# adc.net
KiCad netlist of a schematic drawn in Altium Designer
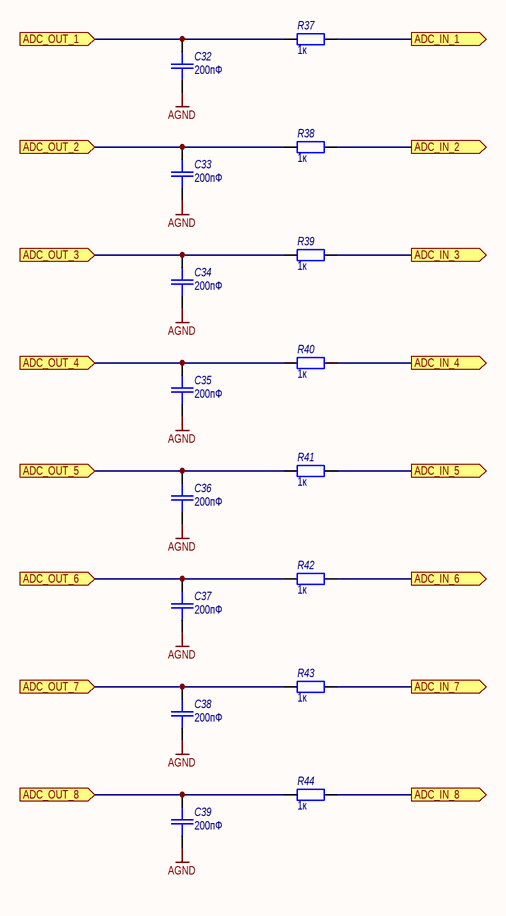
[diagram p0: adc.SchDoc]

(export (version "E")
  (design (tool "Eeschema 10.0.6"))
  (components
    (comp (ref "C32")
      (value "200пФ")
      (footprint "SMD_0805")
      (description "Capacitor")
      (libsource (lib "Passive") (part "Capacitor"))
    )
    (comp (ref "C33")
      (value "200пФ")
      (footprint "SMD_0805")
      (description "Capacitor")
      (libsource (lib "Passive") (part "Capacitor"))
    )
    (comp (ref "C34")
      (value "200пФ")
      (footprint "SMD_0805")
      (description "Capacitor")
      (libsource (lib "Passive") (part "Capacitor"))
    )
    (comp (ref "C35")
      (value "200пФ")
      (footprint "SMD_0805")
      (description "Capacitor")
      (libsource (lib "Passive") (part "Capacitor"))
    )
    (comp (ref "C36")
      (value "200пФ")
      (footprint "SMD_0805")
      (description "Capacitor")
      (libsource (lib "Passive") (part "Capacitor"))
    )
    (comp (ref "C37")
      (value "200пФ")
      (footprint "SMD_0805")
      (description "Capacitor")
      (libsource (lib "Passive") (part "Capacitor"))
    )
    (comp (ref "C38")
      (value "200пФ")
      (footprint "SMD_0805")
      (description "Capacitor")
      (libsource (lib "Passive") (part "Capacitor"))
    )
    (comp (ref "C39")
      (value "200пФ")
      (footprint "SMD_0805")
      (description "Capacitor")
      (libsource (lib "Passive") (part "Capacitor"))
    )
    (comp (ref "R37")
      (value "1к")
      (footprint "SMD_0805")
      (description "Resistor")
      (libsource (lib "Passive") (part "Resistor"))
    )
    (comp (ref "R38")
      (value "1к")
      (footprint "SMD_0805")
      (description "Resistor")
      (libsource (lib "Passive") (part "Resistor"))
    )
    (comp (ref "R39")
      (value "1к")
      (footprint "SMD_0805")
      (description "Resistor")
      (libsource (lib "Passive") (part "Resistor"))
    )
    (comp (ref "R40")
      (value "1к")
      (footprint "SMD_0805")
      (description "Resistor")
      (libsource (lib "Passive") (part "Resistor"))
    )
    (comp (ref "R41")
      (value "1к")
      (footprint "SMD_0805")
      (description "Resistor")
      (libsource (lib "Passive") (part "Resistor"))
    )
    (comp (ref "R42")
      (value "1к")
      (footprint "SMD_0805")
      (description "Resistor")
      (libsource (lib "Passive") (part "Resistor"))
    )
    (comp (ref "R43")
      (value "1к")
      (footprint "SMD_0805")
      (description "Resistor")
      (libsource (lib "Passive") (part "Resistor"))
    )
    (comp (ref "R44")
      (value "1к")
      (footprint "SMD_0805")
      (description "Resistor")
      (libsource (lib "Passive") (part "Resistor"))
    )
  )
  (nets
    (net (code "1") (name "/ADC_IN_1") (class "Default")
      (node (ref "R37") (pin "2") (pinfunction "2_2") (pintype "passive"))
    )
    (net (code "2") (name "/ADC_IN_2") (class "Default")
      (node (ref "R38") (pin "2") (pinfunction "2_2") (pintype "passive"))
    )
    (net (code "3") (name "/ADC_IN_3") (class "Default")
      (node (ref "R39") (pin "2") (pinfunction "2_2") (pintype "passive"))
    )
    (net (code "4") (name "/ADC_IN_4") (class "Default")
      (node (ref "R40") (pin "2") (pinfunction "2_2") (pintype "passive"))
    )
    (net (code "5") (name "/ADC_IN_5") (class "Default")
      (node (ref "R41") (pin "2") (pinfunction "2_2") (pintype "passive"))
    )
    (net (code "6") (name "/ADC_IN_6") (class "Default")
      (node (ref "R42") (pin "2") (pinfunction "2_2") (pintype "passive"))
    )
    (net (code "7") (name "/ADC_IN_7") (class "Default")
      (node (ref "R43") (pin "2") (pinfunction "2_2") (pintype "passive"))
    )
    (net (code "8") (name "/ADC_IN_8") (class "Default")
      (node (ref "R44") (pin "2") (pinfunction "2_2") (pintype "passive"))
    )
    (net (code "9") (name "/ADC_OUT_1") (class "Default")
      (node (ref "C32") (pin "2") (pinfunction "2_2") (pintype "passive"))
      (node (ref "R37") (pin "1") (pinfunction "1_1") (pintype "passive"))
    )
    (net (code "10") (name "/ADC_OUT_2") (class "Default")
      (node (ref "C33") (pin "2") (pinfunction "2_2") (pintype "passive"))
      (node (ref "R38") (pin "1") (pinfunction "1_1") (pintype "passive"))
    )
    (net (code "11") (name "/ADC_OUT_3") (class "Default")
      (node (ref "C34") (pin "2") (pinfunction "2_2") (pintype "passive"))
      (node (ref "R39") (pin "1") (pinfunction "1_1") (pintype "passive"))
    )
    (net (code "12") (name "/ADC_OUT_4") (class "Default")
      (node (ref "C35") (pin "2") (pinfunction "2_2") (pintype "passive"))
      (node (ref "R40") (pin "1") (pinfunction "1_1") (pintype "passive"))
    )
    (net (code "13") (name "/ADC_OUT_5") (class "Default")
      (node (ref "C36") (pin "2") (pinfunction "2_2") (pintype "passive"))
      (node (ref "R41") (pin "1") (pinfunction "1_1") (pintype "passive"))
    )
    (net (code "14") (name "/ADC_OUT_6") (class "Default")
      (node (ref "C37") (pin "2") (pinfunction "2_2") (pintype "passive"))
      (node (ref "R42") (pin "1") (pinfunction "1_1") (pintype "passive"))
    )
    (net (code "15") (name "/ADC_OUT_7") (class "Default")
      (node (ref "C38") (pin "2") (pinfunction "2_2") (pintype "passive"))
      (node (ref "R43") (pin "1") (pinfunction "1_1") (pintype "passive"))
    )
    (net (code "16") (name "/ADC_OUT_8") (class "Default")
      (node (ref "C39") (pin "2") (pinfunction "2_2") (pintype "passive"))
      (node (ref "R44") (pin "1") (pinfunction "1_1") (pintype "passive"))
    )
    (net (code "17") (name "AGND") (class "Default")
      (node (ref "C32") (pin "1") (pinfunction "1_1") (pintype "passive"))
      (node (ref "C33") (pin "1") (pinfunction "1_1") (pintype "passive"))
      (node (ref "C34") (pin "1") (pinfunction "1_1") (pintype "passive"))
      (node (ref "C35") (pin "1") (pinfunction "1_1") (pintype "passive"))
      (node (ref "C36") (pin "1") (pinfunction "1_1") (pintype "passive"))
      (node (ref "C37") (pin "1") (pinfunction "1_1") (pintype "passive"))
      (node (ref "C38") (pin "1") (pinfunction "1_1") (pintype "passive"))
      (node (ref "C39") (pin "1") (pinfunction "1_1") (pintype "passive"))
    )
  )
)
